# Zio_nRF52840_Dev_Board.net
KiCad netlist of a schematic drawn in EAGLE
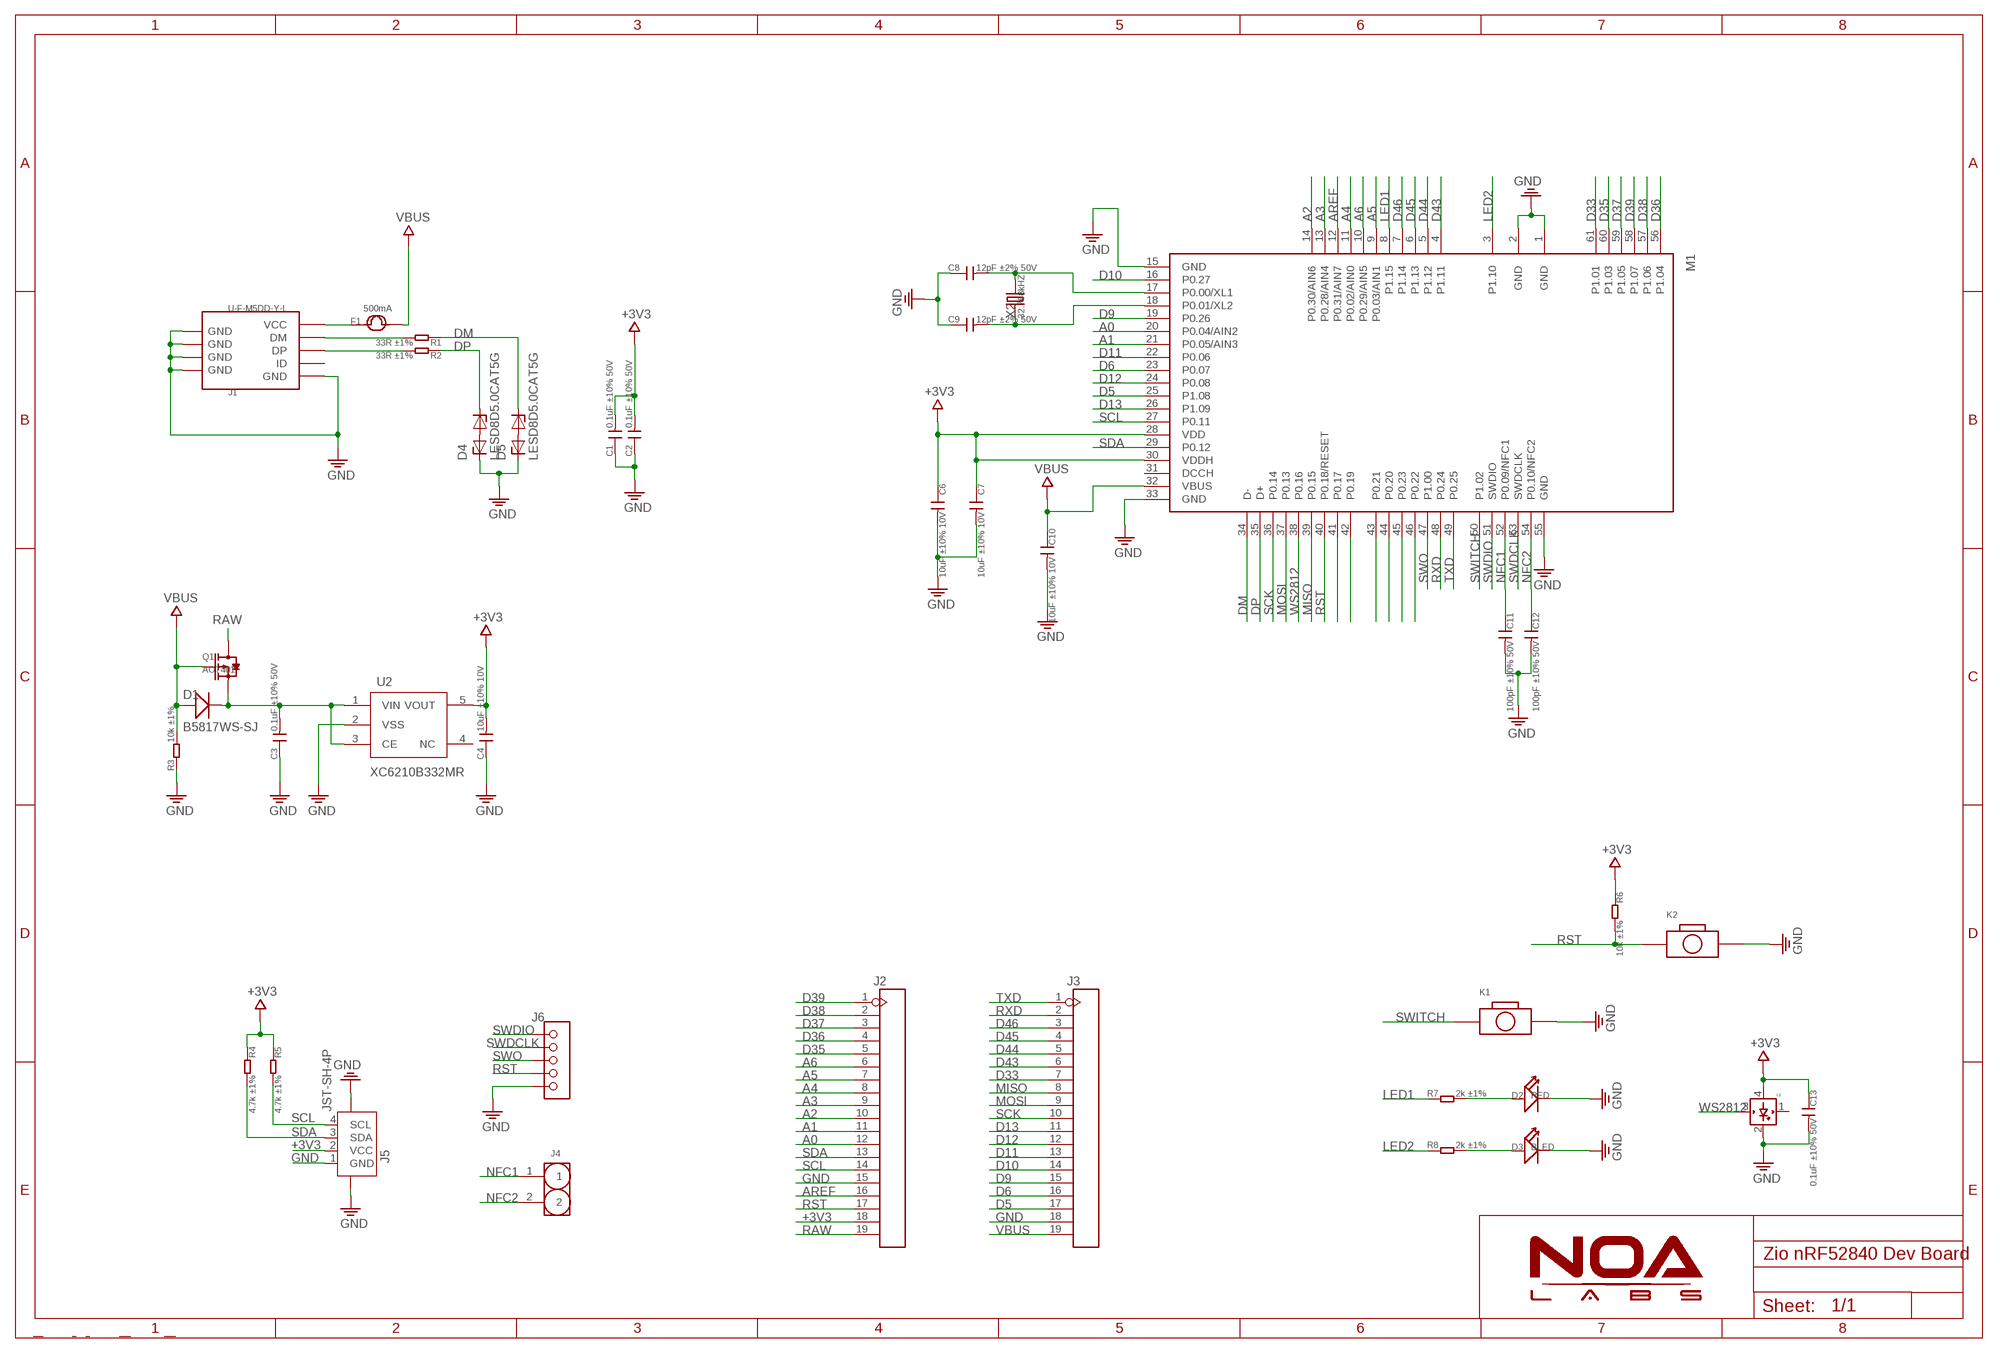
[diagram p0: schematic, sheet 1]

(export (version "E")
  (design (tool "Eeschema 10.0.6"))
  (components
    (comp (ref "C1")
      (value "0.1uF ±10% 50V")
      (footprint "eagle-import:C0402")
      (libsource (lib "eagle-import") (part "C-0402"))
    )
    (comp (ref "C2")
      (value "0.1uF ±10% 50V")
      (footprint "eagle-import:C0402")
      (libsource (lib "eagle-import") (part "C-0402"))
    )
    (comp (ref "C3")
      (value "0.1uF ±10% 50V")
      (footprint "eagle-import:C0402")
      (libsource (lib "eagle-import") (part "C-0402"))
    )
    (comp (ref "C4")
      (value "10uF ±10% 10V")
      (footprint "eagle-import:C0603")
      (libsource (lib "eagle-import") (part "C-0603"))
    )
    (comp (ref "C6")
      (value "10uF ±10% 10V")
      (footprint "eagle-import:C0603")
      (libsource (lib "eagle-import") (part "C-0603"))
    )
    (comp (ref "C7")
      (value "10uF ±10% 10V")
      (footprint "eagle-import:C0603")
      (libsource (lib "eagle-import") (part "C-0603"))
    )
    (comp (ref "C8")
      (value "12pF ±2% 50V")
      (footprint "eagle-import:C0402")
      (libsource (lib "eagle-import") (part "C-0402"))
    )
    (comp (ref "C9")
      (value "12pF ±2% 50V")
      (footprint "eagle-import:C0402")
      (libsource (lib "eagle-import") (part "C-0402"))
    )
    (comp (ref "C10")
      (value "10uF ±10% 10V")
      (footprint "eagle-import:C0603")
      (libsource (lib "eagle-import") (part "C-0603"))
    )
    (comp (ref "C11")
      (value "100pF ±10% 50V")
      (footprint "eagle-import:C0402")
      (libsource (lib "eagle-import") (part "C-0402"))
    )
    (comp (ref "C12")
      (value "100pF ±10% 50V")
      (footprint "eagle-import:C0402")
      (libsource (lib "eagle-import") (part "C-0402"))
    )
    (comp (ref "C13")
      (value "0.1uF ±10% 50V")
      (footprint "eagle-import:C0402")
      (libsource (lib "eagle-import") (part "C-0402"))
    )
    (comp (ref "D1")
      (value "B5817WS-SJ")
      (footprint "eagle-import:SOD323")
      (libsource (lib "eagle-import") (part "D-0805"))
    )
    (comp (ref "D2")
      (value "RED")
      (footprint "eagle-import:LED-0603")
      (libsource (lib "eagle-import") (part "LED'0603'"))
    )
    (comp (ref "D3")
      (value "BLED")
      (footprint "eagle-import:LED-0603")
      (libsource (lib "eagle-import") (part "LED'0603'"))
    )
    (comp (ref "D4")
      (value "LESD8D5.0CAT5G")
      (footprint "eagle-import:SOD882")
      (libsource (lib "eagle-import") (part "PESD5V0F1BL"))
    )
    (comp (ref "D5")
      (value "LESD8D5.0CAT5G")
      (footprint "eagle-import:SOD882")
      (libsource (lib "eagle-import") (part "PESD5V0F1BL"))
    )
    (comp (ref "F1")
      (value "500mA")
      (footprint "eagle-import:1206")
      (libsource (lib "eagle-import") (part "FUSE1206"))
    )
    (comp (ref "J1")
      (value "U-F-M5DD-Y-L")
      (footprint "eagle-import:MICRO-SMD")
      (libsource (lib "eagle-import") (part "USB-MICROE"))
    )
    (comp (ref "J2")
      (value "HEADER-19P")
      (footprint "eagle-import:19P-2.54")
      (libsource (lib "eagle-import") (part "HEADER-19P"))
    )
    (comp (ref "J3")
      (value "HEADER-19P")
      (footprint "eagle-import:19P-2.54")
      (libsource (lib "eagle-import") (part "HEADER-19P"))
    )
    (comp (ref "J4")
      (value "HEADER-2P-65/35MIL")
      (footprint "eagle-import:2P-2.54-65_35MIL")
      (libsource (lib "eagle-import") (part "HEADER-2P-65/35MIL"))
    )
    (comp (ref "J5")
      (value "JST-SH-4P")
      (footprint "eagle-import:JST-SH-4P-90")
      (libsource (lib "eagle-import") (part "JST-SH-4P"))
    )
    (comp (ref "J6")
      (value "HEADER-5P-2.54")
      (footprint "eagle-import:5P-2.54")
      (libsource (lib "eagle-import") (part "HEADER-5P-2.54"))
    )
    (comp (ref "K1")
      (value "BOTTON-2PSKRKAEE020")
      (footprint "eagle-import:SKRKAEE020")
      (libsource (lib "eagle-import") (part "BOTTON-2PSKRKAEE020"))
    )
    (comp (ref "K2")
      (value "BOTTON-2PSKRKAEE020")
      (footprint "eagle-import:SKRKAEE020")
      (libsource (lib "eagle-import") (part "BOTTON-2PSKRKAEE020"))
    )
    (comp (ref "L1")
      (value "WS2812B2020")
      (footprint "eagle-import:WS2812_2020")
      (libsource (lib "eagle-import") (part "WS2812B2020"))
    )
    (comp (ref "M1")
      (value "MDBT50")
      (footprint "eagle-import:MDBT50")
      (libsource (lib "eagle-import") (part "MDBT50"))
    )
    (comp (ref "Q1")
      (value "AO7401")
      (footprint "eagle-import:SOT-323")
      (libsource (lib "eagle-import") (part "MOSFET-P-323"))
    )
    (comp (ref "R1")
      (value "33R ±1%")
      (footprint "eagle-import:R0402")
      (libsource (lib "eagle-import") (part "R-0402"))
    )
    (comp (ref "R2")
      (value "33R ±1%")
      (footprint "eagle-import:R0402")
      (libsource (lib "eagle-import") (part "R-0402"))
    )
    (comp (ref "R3")
      (value "10k ±1%")
      (footprint "eagle-import:R0402")
      (libsource (lib "eagle-import") (part "R-0402"))
    )
    (comp (ref "R4")
      (value "4.7k ±1%")
      (footprint "eagle-import:R0402")
      (libsource (lib "eagle-import") (part "R-0402"))
    )
    (comp (ref "R5")
      (value "4.7k ±1%")
      (footprint "eagle-import:R0402")
      (libsource (lib "eagle-import") (part "R-0402"))
    )
    (comp (ref "R6")
      (value "10k ±1%")
      (footprint "eagle-import:R0402")
      (libsource (lib "eagle-import") (part "R-0402"))
    )
    (comp (ref "R7")
      (value "2k ±1%")
      (footprint "eagle-import:R0402")
      (libsource (lib "eagle-import") (part "R-0402"))
    )
    (comp (ref "R8")
      (value "2k ±1%")
      (footprint "eagle-import:R0402")
      (libsource (lib "eagle-import") (part "R-0402"))
    )
    (comp (ref "U2")
      (value "XC6210B332MR")
      (footprint "eagle-import:SOT23-5")
      (libsource (lib "eagle-import") (part "XC6210"))
    )
    (comp (ref "X2")
      (value "32.768kHZ")
      (footprint "eagle-import:2P-SMD-3.2X1.5")
      (libsource (lib "eagle-import") (part "CRYSTAL-3215"))
    )
  )
  (nets
    (net (code "1") (name "+3V3") (class "Default")
      (node (ref "C1") (pin "2") (pinfunction "2_2") (pintype "passive"))
      (node (ref "C13") (pin "1") (pinfunction "1_1") (pintype "passive"))
      (node (ref "C2") (pin "2") (pinfunction "2_2") (pintype "passive"))
      (node (ref "C4") (pin "2") (pinfunction "2_2") (pintype "passive"))
      (node (ref "C6") (pin "1") (pinfunction "1_1") (pintype "passive"))
      (node (ref "C7") (pin "1") (pinfunction "1_1") (pintype "passive"))
      (node (ref "J2") (pin "18") (pinfunction "P$18_18") (pintype "bidirectional"))
      (node (ref "J5") (pin "2") (pinfunction "VCC_2") (pintype "bidirectional"))
      (node (ref "L1") (pin "4") (pinfunction "VDD_4") (pintype "bidirectional"))
      (node (ref "M1") (pin "28") (pinfunction "VDD_28") (pintype "bidirectional"))
      (node (ref "M1") (pin "30") (pinfunction "VDDH_30") (pintype "bidirectional"))
      (node (ref "R4") (pin "1") (pinfunction "1_1") (pintype "passive"))
      (node (ref "R5") (pin "1") (pinfunction "1_1") (pintype "passive"))
      (node (ref "R6") (pin "1") (pinfunction "1_1") (pintype "passive"))
      (node (ref "U2") (pin "5") (pinfunction "VOUT_5") (pintype "bidirectional"))
    )
    (net (code "2") (name "/A0") (class "Default")
      (node (ref "J2") (pin "12") (pinfunction "P$12_12") (pintype "bidirectional"))
      (node (ref "M1") (pin "20") (pinfunction "P0.04/AIN2_20") (pintype "bidirectional"))
    )
    (net (code "3") (name "/A1") (class "Default")
      (node (ref "J2") (pin "11") (pinfunction "P$11_11") (pintype "bidirectional"))
      (node (ref "M1") (pin "21") (pinfunction "P0.05/AIN3_21") (pintype "bidirectional"))
    )
    (net (code "4") (name "/A2") (class "Default")
      (node (ref "J2") (pin "10") (pinfunction "P$10_10") (pintype "bidirectional"))
      (node (ref "M1") (pin "14") (pinfunction "P0.30/AIN6_14") (pintype "bidirectional"))
    )
    (net (code "5") (name "/A3") (class "Default")
      (node (ref "J2") (pin "9") (pinfunction "P$9_9") (pintype "bidirectional"))
      (node (ref "M1") (pin "13") (pinfunction "P0.28/AIN4_13") (pintype "bidirectional"))
    )
    (net (code "6") (name "/A4") (class "Default")
      (node (ref "J2") (pin "8") (pinfunction "P$8_8") (pintype "bidirectional"))
      (node (ref "M1") (pin "11") (pinfunction "P0.02/AIN0_11") (pintype "bidirectional"))
    )
    (net (code "7") (name "/A5") (class "Default")
      (node (ref "J2") (pin "7") (pinfunction "P$7_7") (pintype "bidirectional"))
      (node (ref "M1") (pin "9") (pinfunction "P0.03/AIN1_9") (pintype "bidirectional"))
    )
    (net (code "8") (name "/A6") (class "Default")
      (node (ref "J2") (pin "6") (pinfunction "P$6_6") (pintype "bidirectional"))
      (node (ref "M1") (pin "10") (pinfunction "P0.29/AIN5_10") (pintype "bidirectional"))
    )
    (net (code "9") (name "/AREF") (class "Default")
      (node (ref "J2") (pin "16") (pinfunction "P$16_16") (pintype "bidirectional"))
      (node (ref "M1") (pin "12") (pinfunction "P0.31/AIN7_12") (pintype "bidirectional"))
    )
    (net (code "10") (name "/D5") (class "Default")
      (node (ref "J3") (pin "17") (pinfunction "P$17_17") (pintype "bidirectional"))
      (node (ref "M1") (pin "25") (pinfunction "P1.08_25") (pintype "bidirectional"))
    )
    (net (code "11") (name "/D6") (class "Default")
      (node (ref "J3") (pin "16") (pinfunction "P$16_16") (pintype "bidirectional"))
      (node (ref "M1") (pin "23") (pinfunction "P0.07_23") (pintype "bidirectional"))
    )
    (net (code "12") (name "/D9") (class "Default")
      (node (ref "J3") (pin "15") (pinfunction "P$15_15") (pintype "bidirectional"))
      (node (ref "M1") (pin "19") (pinfunction "P0.26_19") (pintype "bidirectional"))
    )
    (net (code "13") (name "/D10") (class "Default")
      (node (ref "J3") (pin "14") (pinfunction "P$14_14") (pintype "bidirectional"))
      (node (ref "M1") (pin "16") (pinfunction "P0.27_16") (pintype "bidirectional"))
    )
    (net (code "14") (name "/D11") (class "Default")
      (node (ref "J3") (pin "13") (pinfunction "P$13_13") (pintype "bidirectional"))
      (node (ref "M1") (pin "22") (pinfunction "P0.06_22") (pintype "bidirectional"))
    )
    (net (code "15") (name "/D12") (class "Default")
      (node (ref "J3") (pin "12") (pinfunction "P$12_12") (pintype "bidirectional"))
      (node (ref "M1") (pin "24") (pinfunction "P0.08_24") (pintype "bidirectional"))
    )
    (net (code "16") (name "/D13") (class "Default")
      (node (ref "J3") (pin "11") (pinfunction "P$11_11") (pintype "bidirectional"))
      (node (ref "M1") (pin "26") (pinfunction "P1.09_26") (pintype "bidirectional"))
    )
    (net (code "17") (name "/D33") (class "Default")
      (node (ref "J3") (pin "7") (pinfunction "P$7_7") (pintype "bidirectional"))
      (node (ref "M1") (pin "61") (pinfunction "P1.01_61") (pintype "bidirectional"))
    )
    (net (code "18") (name "/D35") (class "Default")
      (node (ref "J2") (pin "5") (pinfunction "P$5_5") (pintype "bidirectional"))
      (node (ref "M1") (pin "60") (pinfunction "P1.03_60") (pintype "bidirectional"))
    )
    (net (code "19") (name "/D36") (class "Default")
      (node (ref "J2") (pin "4") (pinfunction "P$4_4") (pintype "bidirectional"))
      (node (ref "M1") (pin "56") (pinfunction "P1.04_56") (pintype "bidirectional"))
    )
    (net (code "20") (name "/D37") (class "Default")
      (node (ref "J2") (pin "3") (pinfunction "P$3_3") (pintype "bidirectional"))
      (node (ref "M1") (pin "59") (pinfunction "P1.05_59") (pintype "bidirectional"))
    )
    (net (code "21") (name "/D38") (class "Default")
      (node (ref "J2") (pin "2") (pinfunction "P$2_2") (pintype "bidirectional"))
      (node (ref "M1") (pin "57") (pinfunction "P1.06_57") (pintype "bidirectional"))
    )
    (net (code "22") (name "/D39") (class "Default")
      (node (ref "J2") (pin "1") (pinfunction "P$1_1") (pintype "bidirectional"))
      (node (ref "M1") (pin "58") (pinfunction "P1.07_58") (pintype "bidirectional"))
    )
    (net (code "23") (name "/D43") (class "Default")
      (node (ref "J3") (pin "6") (pinfunction "P$6_6") (pintype "bidirectional"))
      (node (ref "M1") (pin "4") (pinfunction "P1.11_4") (pintype "bidirectional"))
    )
    (net (code "24") (name "/D44") (class "Default")
      (node (ref "J3") (pin "5") (pinfunction "P$5_5") (pintype "bidirectional"))
      (node (ref "M1") (pin "5") (pinfunction "P1.12_5") (pintype "bidirectional"))
    )
    (net (code "25") (name "/D45") (class "Default")
      (node (ref "J3") (pin "4") (pinfunction "P$4_4") (pintype "bidirectional"))
      (node (ref "M1") (pin "6") (pinfunction "P1.13_6") (pintype "bidirectional"))
    )
    (net (code "26") (name "/D46") (class "Default")
      (node (ref "J3") (pin "3") (pinfunction "P$3_3") (pintype "bidirectional"))
      (node (ref "M1") (pin "7") (pinfunction "P1.14_7") (pintype "bidirectional"))
    )
    (net (code "27") (name "/DM") (class "Default")
      (node (ref "D5") (pin "2") (pinfunction "P$2_2") (pintype "bidirectional"))
      (node (ref "M1") (pin "34") (pinfunction "D-_34") (pintype "bidirectional"))
      (node (ref "R1") (pin "1") (pinfunction "1_1") (pintype "passive"))
    )
    (net (code "28") (name "/DP") (class "Default")
      (node (ref "D4") (pin "2") (pinfunction "P$2_2") (pintype "bidirectional"))
      (node (ref "M1") (pin "35") (pinfunction "D+_35") (pintype "bidirectional"))
      (node (ref "R2") (pin "1") (pinfunction "1_1") (pintype "passive"))
    )
    (net (code "29") (name "/LED1") (class "Default")
      (node (ref "M1") (pin "8") (pinfunction "P1.15_8") (pintype "bidirectional"))
      (node (ref "R7") (pin "1") (pinfunction "1_1") (pintype "passive"))
    )
    (net (code "30") (name "/LED2") (class "Default")
      (node (ref "M1") (pin "3") (pinfunction "P1.10_3") (pintype "bidirectional"))
      (node (ref "R8") (pin "1") (pinfunction "1_1") (pintype "passive"))
    )
    (net (code "31") (name "/MISO") (class "Default")
      (node (ref "J3") (pin "8") (pinfunction "P$8_8") (pintype "bidirectional"))
      (node (ref "M1") (pin "39") (pinfunction "P0.15_39") (pintype "bidirectional"))
    )
    (net (code "32") (name "/MOSI") (class "Default")
      (node (ref "J3") (pin "9") (pinfunction "P$9_9") (pintype "bidirectional"))
      (node (ref "M1") (pin "37") (pinfunction "P0.13_37") (pintype "bidirectional"))
    )
    (net (code "33") (name "/NFC1") (class "Default")
      (node (ref "C11") (pin "1") (pinfunction "1_1") (pintype "passive"))
      (node (ref "J4") (pin "1") (pinfunction "1_1") (pintype "bidirectional"))
      (node (ref "M1") (pin "52") (pinfunction "P0.09/NFC1_52") (pintype "bidirectional"))
    )
    (net (code "34") (name "/NFC2") (class "Default")
      (node (ref "C12") (pin "1") (pinfunction "1_1") (pintype "passive"))
      (node (ref "J4") (pin "2") (pinfunction "2_2") (pintype "bidirectional"))
      (node (ref "M1") (pin "54") (pinfunction "P0.10/NFC2_54") (pintype "bidirectional"))
    )
    (net (code "35") (name "/RAW") (class "Default")
      (node (ref "J2") (pin "19") (pinfunction "P$19_19") (pintype "bidirectional"))
      (node (ref "Q1") (pin "3") (pinfunction "D_3") (pintype "passive"))
    )
    (net (code "36") (name "/RST") (class "Default")
      (node (ref "J2") (pin "17") (pinfunction "P$17_17") (pintype "bidirectional"))
      (node (ref "J6") (pin "4") (pinfunction "4_4") (pintype "bidirectional"))
      (node (ref "K2") (pin "1") (pinfunction "1_1") (pintype "bidirectional"))
      (node (ref "M1") (pin "40") (pinfunction "P0.18/RESET_40") (pintype "bidirectional"))
      (node (ref "R6") (pin "2") (pinfunction "2_2") (pintype "passive"))
    )
    (net (code "37") (name "/RXD") (class "Default")
      (node (ref "J3") (pin "2") (pinfunction "P$2_2") (pintype "bidirectional"))
      (node (ref "M1") (pin "48") (pinfunction "P0.24_48") (pintype "bidirectional"))
    )
    (net (code "38") (name "/SCK") (class "Default")
      (node (ref "J3") (pin "10") (pinfunction "P$10_10") (pintype "bidirectional"))
      (node (ref "M1") (pin "36") (pinfunction "P0.14_36") (pintype "bidirectional"))
    )
    (net (code "39") (name "/SCL") (class "Default")
      (node (ref "J2") (pin "14") (pinfunction "P$14_14") (pintype "bidirectional"))
      (node (ref "J5") (pin "4") (pinfunction "SCL_4") (pintype "bidirectional"))
      (node (ref "M1") (pin "27") (pinfunction "P0.11_27") (pintype "bidirectional"))
      (node (ref "R5") (pin "2") (pinfunction "2_2") (pintype "passive"))
    )
    (net (code "40") (name "/SDA") (class "Default")
      (node (ref "J2") (pin "13") (pinfunction "P$13_13") (pintype "bidirectional"))
      (node (ref "J5") (pin "3") (pinfunction "SDA_3") (pintype "bidirectional"))
      (node (ref "M1") (pin "29") (pinfunction "P0.12_29") (pintype "bidirectional"))
      (node (ref "R4") (pin "2") (pinfunction "2_2") (pintype "passive"))
    )
    (net (code "41") (name "/SWDCLK") (class "Default")
      (node (ref "J6") (pin "2") (pinfunction "2_2") (pintype "bidirectional"))
      (node (ref "M1") (pin "53") (pinfunction "SWDCLK_53") (pintype "bidirectional"))
    )
    (net (code "42") (name "/SWDIO") (class "Default")
      (node (ref "J6") (pin "1") (pinfunction "1_1") (pintype "bidirectional"))
      (node (ref "M1") (pin "51") (pinfunction "SWDIO_51") (pintype "bidirectional"))
    )
    (net (code "43") (name "/SWITCH") (class "Default")
      (node (ref "K1") (pin "1") (pinfunction "1_1") (pintype "bidirectional"))
      (node (ref "M1") (pin "50") (pinfunction "P1.02_50") (pintype "bidirectional"))
    )
    (net (code "44") (name "/SWO") (class "Default")
      (node (ref "J6") (pin "3") (pinfunction "3_3") (pintype "bidirectional"))
      (node (ref "M1") (pin "47") (pinfunction "P1.00_47") (pintype "bidirectional"))
    )
    (net (code "45") (name "/TXD") (class "Default")
      (node (ref "J3") (pin "1") (pinfunction "P$1_1") (pintype "bidirectional"))
      (node (ref "M1") (pin "49") (pinfunction "P0.25_49") (pintype "bidirectional"))
    )
    (net (code "46") (name "/WS2812") (class "Default")
      (node (ref "L1") (pin "3") (pinfunction "DIN_3") (pintype "input"))
      (node (ref "M1") (pin "38") (pinfunction "P0.16_38") (pintype "bidirectional"))
    )
    (net (code "47") (name "GND") (class "Default")
      (node (ref "C1") (pin "1") (pinfunction "1_1") (pintype "passive"))
      (node (ref "C10") (pin "2") (pinfunction "2_2") (pintype "passive"))
      (node (ref "C11") (pin "2") (pinfunction "2_2") (pintype "passive"))
      (node (ref "C12") (pin "2") (pinfunction "2_2") (pintype "passive"))
      (node (ref "C13") (pin "2") (pinfunction "2_2") (pintype "passive"))
      (node (ref "C2") (pin "1") (pinfunction "1_1") (pintype "passive"))
      (node (ref "C3") (pin "1") (pinfunction "1_1") (pintype "passive"))
      (node (ref "C4") (pin "1") (pinfunction "1_1") (pintype "passive"))
      (node (ref "C6") (pin "2") (pinfunction "2_2") (pintype "passive"))
      (node (ref "C7") (pin "2") (pinfunction "2_2") (pintype "passive"))
      (node (ref "C8") (pin "1") (pinfunction "1_1") (pintype "passive"))
      (node (ref "C9") (pin "1") (pinfunction "1_1") (pintype "passive"))
      (node (ref "D2") (pin "-") (pinfunction "-_-") (pintype "passive"))
      (node (ref "D3") (pin "-") (pinfunction "-_-") (pintype "passive"))
      (node (ref "D4") (pin "1") (pinfunction "P$1_1") (pintype "bidirectional"))
      (node (ref "D5") (pin "1") (pinfunction "P$1_1") (pintype "bidirectional"))
      (node (ref "J1") (pin "P5") (pinfunction "GND_P5") (pintype "bidirectional"))
      (node (ref "J1") (pin "S1") (pinfunction "GND_S1") (pintype "bidirectional"))
      (node (ref "J1") (pin "S2") (pinfunction "GND_S2") (pintype "bidirectional"))
      (node (ref "J1") (pin "S3") (pinfunction "GND_S3") (pintype "bidirectional"))
      (node (ref "J1") (pin "S4") (pinfunction "GND_S4") (pintype "bidirectional"))
      (node (ref "J2") (pin "15") (pinfunction "P$15_15") (pintype "bidirectional"))
      (node (ref "J3") (pin "18") (pinfunction "P$18_18") (pintype "bidirectional"))
      (node (ref "J5") (pin "1") (pinfunction "GND_1") (pintype "bidirectional"))
      (node (ref "J5") (pin "5") (pinfunction "5_5") (pintype "bidirectional"))
      (node (ref "J5") (pin "6") (pinfunction "6_6") (pintype "bidirectional"))
      (node (ref "J6") (pin "5") (pinfunction "5_5") (pintype "bidirectional"))
      (node (ref "K1") (pin "2") (pinfunction "2_2") (pintype "bidirectional"))
      (node (ref "K2") (pin "2") (pinfunction "2_2") (pintype "bidirectional"))
      (node (ref "L1") (pin "2") (pinfunction "GND_2") (pintype "bidirectional"))
      (node (ref "M1") (pin "1") (pinfunction "GND_1") (pintype "bidirectional"))
      (node (ref "M1") (pin "15") (pinfunction "GND_15") (pintype "bidirectional"))
      (node (ref "M1") (pin "2") (pinfunction "GND_2") (pintype "bidirectional"))
      (node (ref "M1") (pin "33") (pinfunction "GND_33") (pintype "bidirectional"))
      (node (ref "M1") (pin "55") (pinfunction "GND_55") (pintype "bidirectional"))
      (node (ref "R3") (pin "1") (pinfunction "1_1") (pintype "passive"))
      (node (ref "U2") (pin "2") (pinfunction "VSS_2") (pintype "bidirectional"))
    )
    (net (code "48") (name "Net-(D2-Pad+)") (class "Default")
      (node (ref "D2") (pin "+") (pinfunction "+_+") (pintype "passive"))
      (node (ref "R7") (pin "2") (pinfunction "2_2") (pintype "passive"))
    )
    (net (code "49") (name "Net-(D3-Pad+)") (class "Default")
      (node (ref "D3") (pin "+") (pinfunction "+_+") (pintype "passive"))
      (node (ref "R8") (pin "2") (pinfunction "2_2") (pintype "passive"))
    )
    (net (code "50") (name "Net-(J1-DM)") (class "Default")
      (node (ref "J1") (pin "P2") (pinfunction "DM_P2") (pintype "bidirectional"))
      (node (ref "R1") (pin "2") (pinfunction "2_2") (pintype "passive"))
    )
    (net (code "51") (name "Net-(J1-DP)") (class "Default")
      (node (ref "J1") (pin "P3") (pinfunction "DP_P3") (pintype "bidirectional"))
      (node (ref "R2") (pin "2") (pinfunction "2_2") (pintype "passive"))
    )
    (net (code "52") (name "Net-(J1-VCC)") (class "Default")
      (node (ref "F1") (pin "1") (pinfunction "1_1") (pintype "bidirectional"))
      (node (ref "J1") (pin "P1") (pinfunction "VCC_P1") (pintype "bidirectional"))
    )
    (net (code "53") (name "Net-(M1-P0.00{slash}XL1)") (class "Default")
      (node (ref "C8") (pin "2") (pinfunction "2_2") (pintype "passive"))
      (node (ref "M1") (pin "17") (pinfunction "P0.00/XL1_17") (pintype "bidirectional"))
      (node (ref "X2") (pin "2") (pinfunction "2_2") (pintype "passive"))
    )
    (net (code "54") (name "Net-(M1-P0.01{slash}XL2)") (class "Default")
      (node (ref "C9") (pin "2") (pinfunction "2_2") (pintype "passive"))
      (node (ref "M1") (pin "18") (pinfunction "P0.01/XL2_18") (pintype "bidirectional"))
      (node (ref "X2") (pin "1") (pinfunction "1_1") (pintype "passive"))
    )
    (net (code "55") (name "Net-(Q1-S)") (class "Default")
      (node (ref "C3") (pin "2") (pinfunction "2_2") (pintype "passive"))
      (node (ref "D1") (pin "-") (pinfunction "-_-") (pintype "passive"))
      (node (ref "Q1") (pin "2") (pinfunction "S_2") (pintype "passive"))
      (node (ref "U2") (pin "1") (pinfunction "VIN_1") (pintype "bidirectional"))
      (node (ref "U2") (pin "3") (pinfunction "CE_3") (pintype "bidirectional"))
    )
    (net (code "56") (name "VBUS") (class "Default")
      (node (ref "C10") (pin "1") (pinfunction "1_1") (pintype "passive"))
      (node (ref "D1") (pin "+") (pinfunction "+_+") (pintype "passive"))
      (node (ref "F1") (pin "2") (pinfunction "2_2") (pintype "bidirectional"))
      (node (ref "J3") (pin "19") (pinfunction "P$19_19") (pintype "bidirectional"))
      (node (ref "M1") (pin "32") (pinfunction "VBUS_32") (pintype "bidirectional"))
      (node (ref "Q1") (pin "1") (pinfunction "G_1") (pintype "passive"))
      (node (ref "R3") (pin "2") (pinfunction "2_2") (pintype "passive"))
    )
    (net (code "57") (name "unconnected-(J1-ID-PadP4)") (class "Default")
      (node (ref "J1") (pin "P4") (pinfunction "ID_P4") (pintype "bidirectional"))
    )
    (net (code "58") (name "unconnected-(L1-DOUT-Pad1)") (class "Default")
      (node (ref "L1") (pin "1") (pinfunction "DOUT_1") (pintype "output"))
    )
    (net (code "59") (name "unconnected-(M1-DCCH-Pad31)") (class "Default")
      (node (ref "M1") (pin "31") (pinfunction "DCCH_31") (pintype "bidirectional"))
    )
    (net (code "60") (name "unconnected-(M1-P0.17-Pad41)") (class "Default")
      (node (ref "M1") (pin "41") (pinfunction "P0.17_41") (pintype "bidirectional"))
    )
    (net (code "61") (name "unconnected-(M1-P0.19-Pad42)") (class "Default")
      (node (ref "M1") (pin "42") (pinfunction "P0.19_42") (pintype "bidirectional"))
    )
    (net (code "62") (name "unconnected-(M1-P0.20-Pad44)") (class "Default")
      (node (ref "M1") (pin "44") (pinfunction "P0.20_44") (pintype "bidirectional"))
    )
    (net (code "63") (name "unconnected-(M1-P0.21-Pad43)") (class "Default")
      (node (ref "M1") (pin "43") (pinfunction "P0.21_43") (pintype "bidirectional"))
    )
    (net (code "64") (name "unconnected-(M1-P0.22-Pad46)") (class "Default")
      (node (ref "M1") (pin "46") (pinfunction "P0.22_46") (pintype "bidirectional"))
    )
    (net (code "65") (name "unconnected-(M1-P0.23-Pad45)") (class "Default")
      (node (ref "M1") (pin "45") (pinfunction "P0.23_45") (pintype "bidirectional"))
    )
    (net (code "66") (name "unconnected-(U2-NC-Pad4)") (class "Default")
      (node (ref "U2") (pin "4") (pinfunction "NC_4") (pintype "bidirectional"))
    )
  )
)
